# SCH_USB_breakout_2021-07-08.net
KiCad netlist of a schematic drawn in EasyEDA
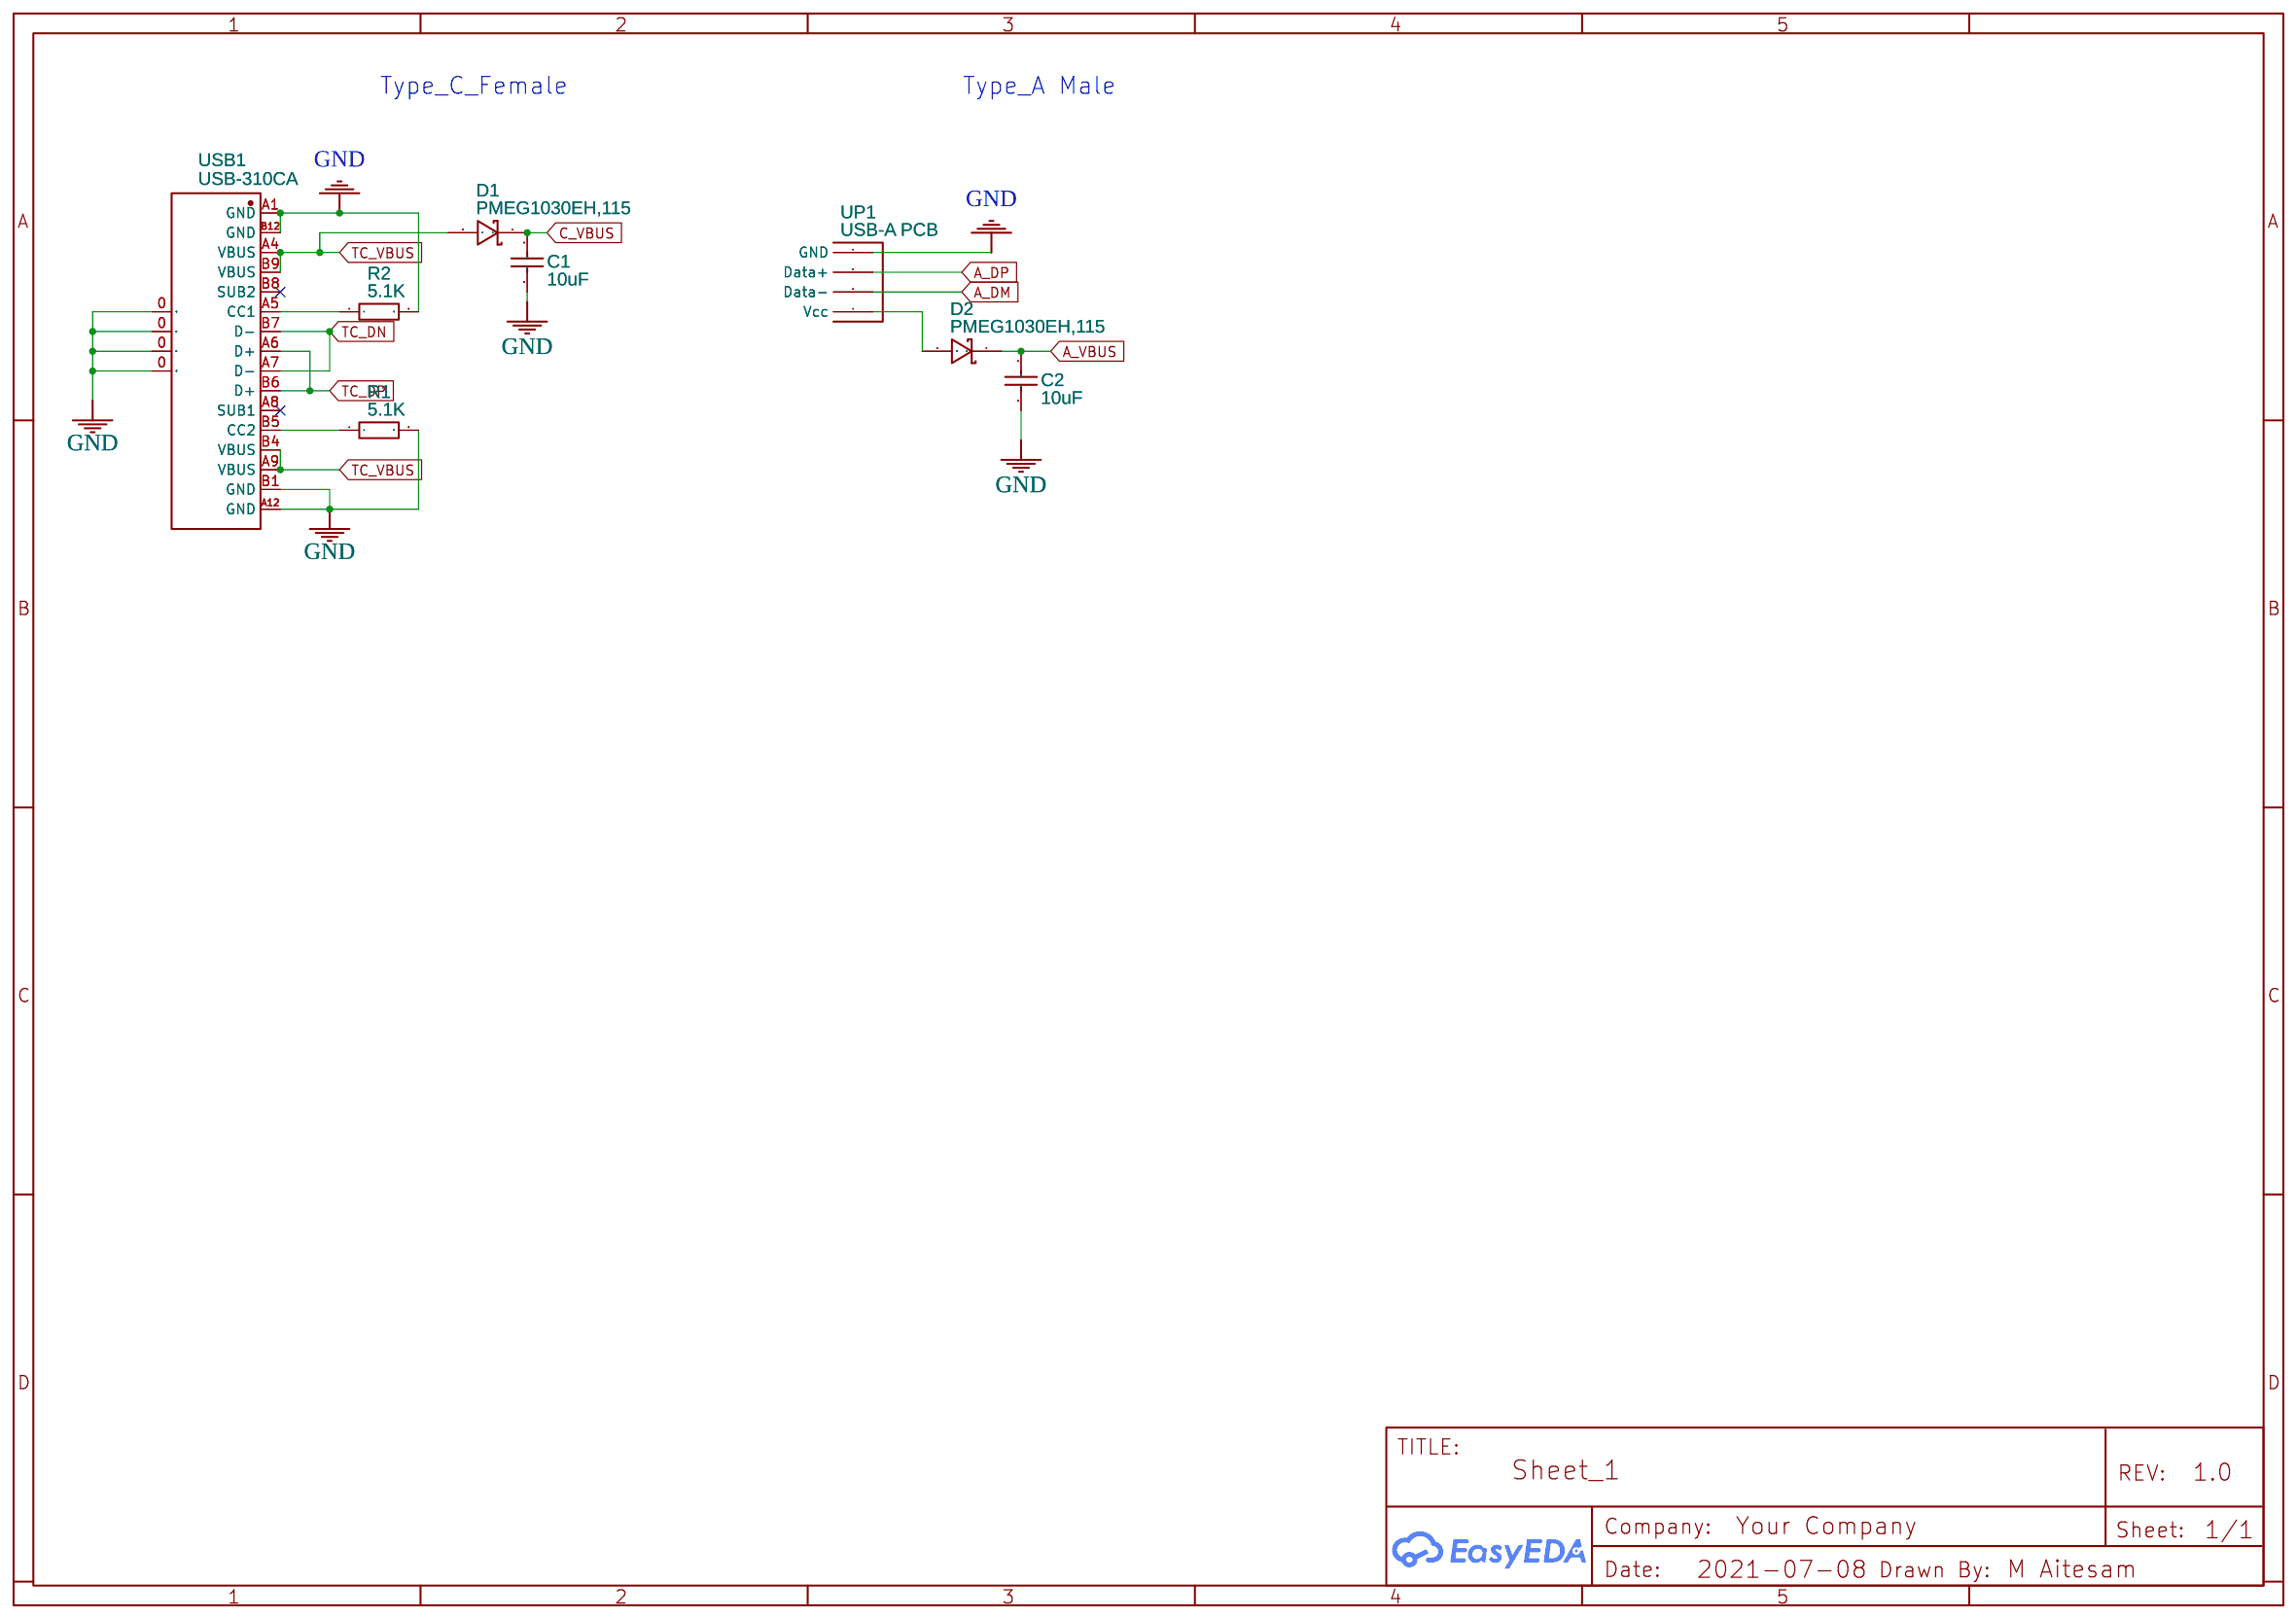
[diagram p0: schematic sheet]

(export (version "E")
  (design (tool "Eeschema 10.0.6"))
  (components
    (comp (ref "C1")
      (value "10uF")
      (fields
        (field (name "BOM_Manufacturer Part") "CL21A106KOQNNNE")
        (field (name "BOM_Supplier Part") "C1713")
      )
      (libsource (lib "") (part "CL21A106KOQNNNE"))
    )
    (comp (ref "C2")
      (value "10uF")
      (fields
        (field (name "BOM_Manufacturer Part") "CL21A106KOQNNNE")
        (field (name "BOM_Supplier Part") "C1713")
      )
      (libsource (lib "") (part "CL21A106KOQNNNE"))
    )
    (comp (ref "D1")
      (value "PMEG1030EH,115")
      (fields (field (name "BOM_Supplier Part") "C552800"))
      (libsource (lib "") (part "PMEG1030EH,115"))
    )
    (comp (ref "D2")
      (value "PMEG1030EH,115")
      (fields (field (name "BOM_Supplier Part") "C552800"))
      (libsource (lib "") (part "PMEG1030EH,115"))
    )
    (comp (ref "R1")
      (value "5.1K")
      (fields
        (field (name "BOM_Manufacturer Part") "RS-03K512JT")
        (field (name "BOM_Supplier Part") "C73801")
      )
      (libsource (lib "") (part "RS-03K512JT"))
    )
    (comp (ref "R2")
      (value "5.1K")
      (fields
        (field (name "BOM_Manufacturer Part") "RS-03K512JT")
        (field (name "BOM_Supplier Part") "C73801")
      )
      (libsource (lib "") (part "RS-03K512JT"))
    )
    (comp (ref "UP1")
      (value "USB-A PCB")
      (fields (field (name "BOM_Manufacturer Part") "New SchematicLib"))
      (libsource (lib "") (part "USB-A PCB"))
    )
    (comp (ref "USB1")
      (value "USB-310CA")
      (fields (field (name "BOM_Supplier Part") "C309372"))
      (libsource (lib "") (part "USB-310CA"))
    )
  )
  (nets
    (net (code "1") (name "A_DM") (class "Default")
      (node (ref "UP1") (pin "3") (pinfunction "Data-_3") (pintype "unspecified"))
    )
    (net (code "2") (name "A_DP") (class "Default")
      (node (ref "UP1") (pin "2") (pinfunction "Data+_2") (pintype "unspecified"))
    )
    (net (code "3") (name "A_VBUS") (class "Default")
      (node (ref "C2") (pin "2") (pinfunction "2_2") (pintype "input"))
      (node (ref "D2") (pin "1") (pinfunction "1_1") (pintype "unspecified"))
    )
    (net (code "4") (name "C_VBUS") (class "Default")
      (node (ref "C1") (pin "2") (pinfunction "2_2") (pintype "input"))
      (node (ref "D1") (pin "1") (pinfunction "1_1") (pintype "unspecified"))
    )
    (net (code "5") (name "GND") (class "Default")
      (node (ref "C1") (pin "1") (pinfunction "1_1") (pintype "input"))
      (node (ref "C2") (pin "1") (pinfunction "1_1") (pintype "input"))
      (node (ref "R1") (pin "2") (pinfunction "2_2") (pintype "input"))
      (node (ref "R2") (pin "2") (pinfunction "2_2") (pintype "input"))
      (node (ref "UP1") (pin "1") (pinfunction "GND_1") (pintype "unspecified"))
      (node (ref "USB1") (pin "0") (pinfunction "0_0") (pintype "unspecified"))
      (node (ref "USB1") (pin "A1") (pinfunction "GND_A1") (pintype "unspecified"))
      (node (ref "USB1") (pin "A12") (pinfunction "GND_A12") (pintype "unspecified"))
      (node (ref "USB1") (pin "B1") (pinfunction "GND_B1") (pintype "unspecified"))
      (node (ref "USB1") (pin "B12") (pinfunction "GND_B12") (pintype "unspecified"))
    )
    (net (code "6") (name "Net-(UP1-Vcc)") (class "Default")
      (node (ref "D2") (pin "2") (pinfunction "2_2") (pintype "unspecified"))
      (node (ref "UP1") (pin "4") (pinfunction "Vcc_4") (pintype "unspecified"))
    )
    (net (code "7") (name "Net-(USB1-CC1)") (class "Default")
      (node (ref "R2") (pin "1") (pinfunction "1_1") (pintype "input"))
      (node (ref "USB1") (pin "A5") (pinfunction "CC1_A5") (pintype "unspecified"))
    )
    (net (code "8") (name "Net-(USB1-CC2)") (class "Default")
      (node (ref "R1") (pin "1") (pinfunction "1_1") (pintype "input"))
      (node (ref "USB1") (pin "B5") (pinfunction "CC2_B5") (pintype "unspecified"))
    )
    (net (code "9") (name "TC_DN") (class "Default")
      (node (ref "USB1") (pin "A7") (pinfunction "D-_A7") (pintype "unspecified"))
      (node (ref "USB1") (pin "B7") (pinfunction "D-_B7") (pintype "unspecified"))
    )
    (net (code "10") (name "TC_DP") (class "Default")
      (node (ref "USB1") (pin "A6") (pinfunction "D+_A6") (pintype "unspecified"))
      (node (ref "USB1") (pin "B6") (pinfunction "D+_B6") (pintype "unspecified"))
    )
    (net (code "11") (name "TC_VBUS") (class "Default")
      (node (ref "D1") (pin "2") (pinfunction "2_2") (pintype "unspecified"))
      (node (ref "USB1") (pin "A4") (pinfunction "VBUS_A4") (pintype "unspecified"))
      (node (ref "USB1") (pin "A9") (pinfunction "VBUS_A9") (pintype "unspecified"))
      (node (ref "USB1") (pin "B4") (pinfunction "VBUS_B4") (pintype "unspecified"))
      (node (ref "USB1") (pin "B9") (pinfunction "VBUS_B9") (pintype "unspecified"))
    )
    (net (code "12") (name "unconnected-(USB1-SUB1-PadA8)") (class "Default")
      (node (ref "USB1") (pin "A8") (pinfunction "SUB1_A8") (pintype "unspecified+no_connect"))
    )
    (net (code "13") (name "unconnected-(USB1-SUB2-PadB8)") (class "Default")
      (node (ref "USB1") (pin "B8") (pinfunction "SUB2_B8") (pintype "unspecified+no_connect"))
    )
  )
)
